# ESP8266_PWR_CTRL.net
KiCad netlist of a schematic drawn in Altium Designer
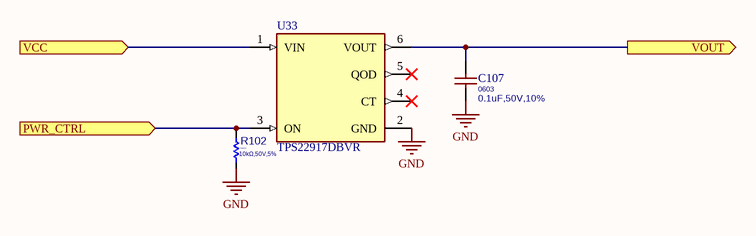
[diagram p0: ESP8266_PWR_CTRL.SchDoc]

(export (version "E")
  (design (tool "Eeschema 10.0.6"))
  (components
    (comp (ref "C107")
      (value "0.1uF,50V,10%")
      (footprint "C0603")
      (description "CAP CER 0.1UF 50V X7R 0603")
      (fields
        (field (name "MANUFACTURER") "Murata Electronics")
        (field (name "MPN") "GCM188R71H104KA57J")
        (field (name "PACKAGE") "0603")
      )
      (libsource (lib "RCL") (part "GCM188R71H104KA57J"))
    )
    (comp (ref "R102")
      (value "10kΩ,50V,5%")
      (footprint "R0402")
      (description "62.5mW Thick Film Resistors 50V ±100ppm/℃ ±5% 10kΩ 0402 Chip Resistor - Surface Mount ROHS")
      (fields
        (field (name "MANUFACTURER") "YAGEO")
        (field (name "MPN") "RC0402JR-0710KL")
        (field (name "PACKAGE") "0402")
      )
      (libsource (lib "RCL") (part "RC0402JR-0710KL"))
    )
    (comp (ref "U33")
      (value "TPS22917DBVR")
      (footprint "SOT95P280X145-6N")
      (description "5.5-V, 2-A, 80-mÎ© , 10-nA leakage load switch adj. rise time and adj output discharge")
      (fields (field (name "MF") "Texas Instruments"))
      (libsource (lib "IC") (part "TPS22917DBVR"))
    )
  )
  (nets
    (net (code "1") (name "/PWR_CTRL") (class "Default")
      (node (ref "R102") (pin "2") (pinfunction "2_2") (pintype "passive"))
      (node (ref "U33") (pin "3") (pinfunction "ON_3") (pintype "input"))
    )
    (net (code "2") (name "/VCC") (class "Default")
      (node (ref "U33") (pin "1") (pinfunction "VIN_1") (pintype "input"))
    )
    (net (code "3") (name "/VOUT") (class "Default")
      (node (ref "C107") (pin "2") (pinfunction "2_2") (pintype "passive"))
      (node (ref "U33") (pin "6") (pinfunction "VOUT_6") (pintype "output"))
    )
    (net (code "4") (name "GND") (class "Default")
      (node (ref "C107") (pin "1") (pinfunction "1_1") (pintype "passive"))
      (node (ref "R102") (pin "1") (pinfunction "1_1") (pintype "passive"))
      (node (ref "U33") (pin "2") (pinfunction "GND_2") (pintype "power_in"))
    )
    (net (code "5") (name "unconnected-(U33-CT-Pad4)") (class "Default")
      (node (ref "U33") (pin "4") (pinfunction "CT_4") (pintype "output+no_connect"))
    )
    (net (code "6") (name "unconnected-(U33-QOD-Pad5)") (class "Default")
      (node (ref "U33") (pin "5") (pinfunction "QOD_5") (pintype "output+no_connect"))
    )
  )
)
